# usb-to-5v.net
KiCad netlist of a schematic drawn in EAGLE
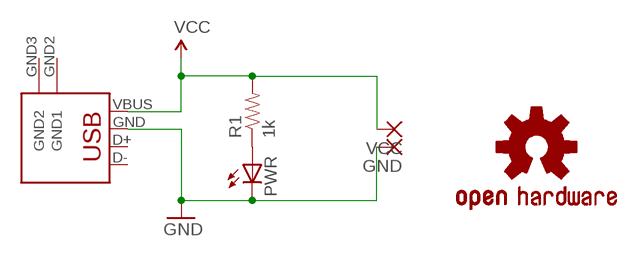
[diagram p0: schematic, sheet 1]

(export (version "E")
  (design (tool "Eeschema 10.0.6"))
  (components
    (comp (ref "GND")
      (value "1,6/0,9")
      (footprint "eagle-import:1,6_0,9")
      (libsource (lib "eagle-import") (part "1,6/0,9"))
    )
    (comp (ref "JP1")
      (value "USB-A-H")
      (footprint "eagle-import:USB-A-H")
      (libsource (lib "eagle-import") (part "USB-A-H"))
    )
    (comp (ref "LOGO1")
      (value "OSHW-LOGOS")
      (footprint "eagle-import:OSHW-LOGO-S")
      (libsource (lib "eagle-import") (part "OSHW-LOGOS"))
    )
    (comp (ref "PWR")
      (value "LED0805")
      (footprint "eagle-import:0805-LED")
      (libsource (lib "eagle-import") (part "LED0805"))
    )
    (comp (ref "R1")
      (value "1k")
      (footprint "eagle-import:0805-RC")
      (libsource (lib "eagle-import") (part "RESISTOR0805"))
    )
    (comp (ref "VCC")
      (value "1,6/0,9")
      (footprint "eagle-import:1,6_0,9")
      (libsource (lib "eagle-import") (part "1,6/0,9"))
    )
  )
  (nets
    (net (code "1") (name "GND") (class "Default")
      (node (ref "GND") (pin "1") (pinfunction "P_1") (pintype "passive"))
      (node (ref "JP1") (pin "GND") (pinfunction "VBUS_GND") (pintype "bidirectional"))
      (node (ref "PWR") (pin "C") (pinfunction "C_C") (pintype "passive"))
    )
    (net (code "2") (name "Net-(PWR-PadA)") (class "Default")
      (node (ref "PWR") (pin "A") (pinfunction "A_A") (pintype "passive"))
      (node (ref "R1") (pin "1") (pinfunction "1_1") (pintype "passive"))
    )
    (net (code "3") (name "VCC") (class "Default")
      (node (ref "JP1") (pin "VBUS") (pinfunction "GND_VBUS") (pintype "bidirectional"))
      (node (ref "R1") (pin "2") (pinfunction "2_2") (pintype "passive"))
      (node (ref "VCC") (pin "1") (pinfunction "P_1") (pintype "passive"))
    )
    (net (code "4") (name "unconnected-(JP1-D+-PadD-)") (class "Default")
      (node (ref "JP1") (pin "D-") (pinfunction "D+_D-") (pintype "bidirectional"))
    )
    (net (code "5") (name "unconnected-(JP1-D--PadD+)") (class "Default")
      (node (ref "JP1") (pin "D+") (pinfunction "D-_D+") (pintype "bidirectional"))
    )
    (net (code "6") (name "unconnected-(JP1-GND1-PadGND2)") (class "Default")
      (node (ref "JP1") (pin "GND2") (pinfunction "GND1_GND2") (pintype "bidirectional"))
    )
    (net (code "7") (name "unconnected-(JP1-GND2-PadGND3)") (class "Default")
      (node (ref "JP1") (pin "GND3") (pinfunction "GND2_GND3") (pintype "bidirectional"))
    )
  )
)
